# Main_Schematic.net
KiCad netlist of a schematic drawn in Altium Designer
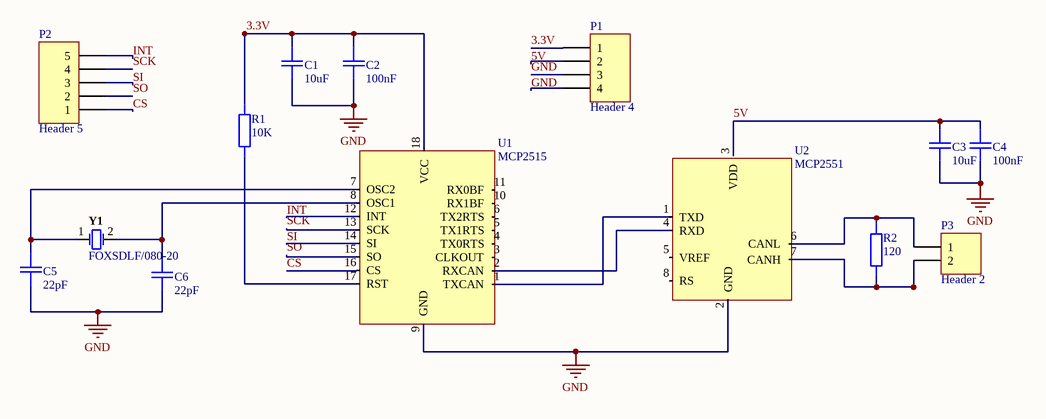
[diagram p0: Main Schematic.SchDoc]

(export (version "E")
  (design (tool "Eeschema 10.0.6"))
  (components
    (comp (ref "C1")
      (value "10uF")
      (footprint "CAP0805")
      (fields
        (field (name "VOLTAGE") "10V")
        (field (name "TOLERANCE") "20%")
        (field (name "Comment") "Capacitor")
      )
      (libsource (lib "Orbit") (part "Capacitor"))
    )
    (comp (ref "C2")
      (value "100nF")
      (footprint "CAP0805")
      (fields
        (field (name "VOLTAGE") "16V")
        (field (name "TOLERANCE") "10%")
        (field (name "Comment") "Capacitor")
      )
      (libsource (lib "Orbit") (part "Capacitor"))
    )
    (comp (ref "C3")
      (value "10uF")
      (footprint "CAP0805")
      (fields
        (field (name "VOLTAGE") "10V")
        (field (name "TOLERANCE") "20%")
        (field (name "Comment") "Capacitor")
      )
      (libsource (lib "Orbit") (part "Capacitor"))
    )
    (comp (ref "C4")
      (value "100nF")
      (footprint "CAP0805")
      (fields
        (field (name "VOLTAGE") "16V")
        (field (name "TOLERANCE") "10%")
        (field (name "Comment") "Capacitor")
      )
      (libsource (lib "Orbit") (part "Capacitor"))
    )
    (comp (ref "C5")
      (value "22pF")
      (footprint "CAP0805")
      (fields
        (field (name "VOLTAGE") "16V")
        (field (name "TOLERANCE") "10%")
        (field (name "Comment") "Capacitor")
      )
      (libsource (lib "Orbit") (part "Capacitor"))
    )
    (comp (ref "C6")
      (value "22pF")
      (footprint "CAP0805")
      (fields
        (field (name "VOLTAGE") "16V")
        (field (name "TOLERANCE") "10%")
        (field (name "Comment") "Capacitor")
      )
      (libsource (lib "Orbit") (part "Capacitor"))
    )
    (comp (ref "P1")
      (value "Header 4")
      (footprint "HDR1X4")
      (description "Header, 4-Pin")
      (fields (field (name "PUBLISHER") "Altium Limited"))
      (libsource (lib "Miscellaneous Connectors") (part "Header 4"))
    )
    (comp (ref "P2")
      (value "Header 5")
      (footprint "HDR1X5")
      (description "Header, 5-Pin")
      (fields (field (name "PUBLISHER") "Altium Limited"))
      (libsource (lib "Miscellaneous Connectors") (part "Header 5"))
    )
    (comp (ref "P3")
      (value "Header 2")
      (footprint "HDR1X2")
      (description "Header, 2-Pin")
      (fields (field (name "PUBLISHER") "Altium Limited"))
      (libsource (lib "Miscellaneous Connectors") (part "Header 2"))
    )
    (comp (ref "R1")
      (value "10K")
      (footprint "6-0805_L")
      (fields (field (name "TOLERANCE") "1%") (field (name "Comment") "Resistor"))
      (libsource (lib "Orbit") (part "Resistor"))
    )
    (comp (ref "R2")
      (value "120")
      (footprint "6-0805_L")
      (fields (field (name "TOLERANCE") "1%") (field (name "Comment") "Resistor"))
      (libsource (lib "Orbit") (part "Resistor"))
    )
    (comp (ref "U1")
      (value "MCP2515")
      (footprint "TSSOP 20-lead 4.4mm")
      (libsource (lib "Orbit") (part "MCP2515"))
    )
    (comp (ref "U2")
      (value "MCP2551")
      (footprint "SOIC 8-LEAD SN")
      (libsource (lib "Orbit") (part "MCP2551"))
    )
    (comp (ref "Y1")
      (value "FOXSDLF/080-20")
      (footprint "FOX-HC49SDLF_V")
      (description "Resistance Weld Crystal, 8 MHz, +/- 30 ppm, -20 to 70 degC, 2-Pin SMD, RoHS, Tape and Reel")
      (fields (field (name "MANUFACTURER") "FOX Electronics") (field (name "TOLERANCE") "50ppm"))
      (libsource (lib "Altium Content Vault") (part "XTAL-1-2-2"))
    )
  )
  (nets
    (net (code "1") (name "/3.3V") (class "Default")
      (node (ref "C1") (pin "1") (pinfunction "1_1") (pintype "passive"))
      (node (ref "C2") (pin "1") (pinfunction "1_1") (pintype "passive"))
      (node (ref "P1") (pin "1") (pinfunction "1_1") (pintype "passive"))
      (node (ref "R1") (pin "2") (pinfunction "2_2") (pintype "passive"))
      (node (ref "U1") (pin "18") (pinfunction "VCC_18") (pintype "power_in"))
    )
    (net (code "2") (name "/5V") (class "Default")
      (node (ref "C3") (pin "1") (pinfunction "1_1") (pintype "passive"))
      (node (ref "C4") (pin "1") (pinfunction "1_1") (pintype "passive"))
      (node (ref "P1") (pin "2") (pinfunction "2_2") (pintype "passive"))
      (node (ref "U2") (pin "3") (pinfunction "VDD_3") (pintype "power_in"))
    )
    (net (code "3") (name "/CS") (class "Default")
      (node (ref "P2") (pin "1") (pinfunction "1_1") (pintype "passive"))
      (node (ref "U1") (pin "16") (pinfunction "CS_16") (pintype "passive"))
    )
    (net (code "4") (name "/INT") (class "Default")
      (node (ref "P2") (pin "5") (pinfunction "5_5") (pintype "passive"))
      (node (ref "U1") (pin "12") (pinfunction "INT_12") (pintype "passive"))
    )
    (net (code "5") (name "/SCK") (class "Default")
      (node (ref "P2") (pin "4") (pinfunction "4_4") (pintype "passive"))
      (node (ref "U1") (pin "13") (pinfunction "SCK_13") (pintype "input"))
    )
    (net (code "6") (name "/SI") (class "Default")
      (node (ref "P2") (pin "3") (pinfunction "3_3") (pintype "passive"))
      (node (ref "U1") (pin "14") (pinfunction "SI_14") (pintype "input"))
    )
    (net (code "7") (name "/SO") (class "Default")
      (node (ref "P2") (pin "2") (pinfunction "2_2") (pintype "passive"))
      (node (ref "U1") (pin "15") (pinfunction "SO_15") (pintype "output"))
    )
    (net (code "8") (name "GND") (class "Default")
      (node (ref "C1") (pin "2") (pinfunction "2_2") (pintype "passive"))
      (node (ref "C2") (pin "2") (pinfunction "2_2") (pintype "passive"))
      (node (ref "C3") (pin "2") (pinfunction "2_2") (pintype "passive"))
      (node (ref "C4") (pin "2") (pinfunction "2_2") (pintype "passive"))
      (node (ref "C5") (pin "2") (pinfunction "2_2") (pintype "passive"))
      (node (ref "C6") (pin "2") (pinfunction "2_2") (pintype "passive"))
      (node (ref "P1") (pin "3") (pinfunction "3_3") (pintype "passive"))
      (node (ref "P1") (pin "4") (pinfunction "4_4") (pintype "passive"))
      (node (ref "U1") (pin "9") (pinfunction "GND_9") (pintype "power_in"))
      (node (ref "U2") (pin "2") (pinfunction "GND_2") (pintype "power_in"))
    )
    (net (code "9") (name "Net-(U1-OSC1)") (class "Default")
      (node (ref "C6") (pin "1") (pinfunction "1_1") (pintype "passive"))
      (node (ref "U1") (pin "8") (pinfunction "OSC1_8") (pintype "passive"))
      (node (ref "Y1") (pin "2") (pinfunction "2_2") (pintype "passive"))
    )
    (net (code "10") (name "Net-(U1-OSC2)") (class "Default")
      (node (ref "C5") (pin "1") (pinfunction "1_1") (pintype "passive"))
      (node (ref "U1") (pin "7") (pinfunction "OSC2_7") (pintype "passive"))
      (node (ref "Y1") (pin "1") (pinfunction "1_1") (pintype "passive"))
    )
    (net (code "11") (name "Net-(U1-RST)") (class "Default")
      (node (ref "R1") (pin "1") (pinfunction "1_1") (pintype "passive"))
      (node (ref "U1") (pin "17") (pinfunction "RST_17") (pintype "passive"))
    )
    (net (code "12") (name "Net-(U1-RXCAN)") (class "Default")
      (node (ref "U1") (pin "2") (pinfunction "RXCAN_2") (pintype "passive"))
      (node (ref "U2") (pin "4") (pinfunction "RXD_4") (pintype "input"))
    )
    (net (code "13") (name "Net-(U1-TXCAN)") (class "Default")
      (node (ref "U1") (pin "1") (pinfunction "TXCAN_1") (pintype "passive"))
      (node (ref "U2") (pin "1") (pinfunction "TXD_1") (pintype "output"))
    )
    (net (code "14") (name "Net-(U2-CANH)") (class "Default")
      (node (ref "P3") (pin "2") (pinfunction "2_2") (pintype "passive"))
      (node (ref "R2") (pin "1") (pinfunction "1_1") (pintype "passive"))
      (node (ref "U2") (pin "7") (pinfunction "CANH_7") (pintype "bidirectional"))
    )
    (net (code "15") (name "Net-(U2-CANL)") (class "Default")
      (node (ref "P3") (pin "1") (pinfunction "1_1") (pintype "passive"))
      (node (ref "R2") (pin "2") (pinfunction "2_2") (pintype "passive"))
      (node (ref "U2") (pin "6") (pinfunction "CANL_6") (pintype "bidirectional"))
    )
    (net (code "16") (name "unconnected-(U1-CLKOUT-Pad3)") (class "Default")
      (node (ref "U1") (pin "3") (pinfunction "CLKOUT_3") (pintype "passive"))
    )
    (net (code "17") (name "unconnected-(U1-RX0BF-Pad11)") (class "Default")
      (node (ref "U1") (pin "11") (pinfunction "RX0BF_11") (pintype "passive"))
    )
    (net (code "18") (name "unconnected-(U1-RX1BF-Pad10)") (class "Default")
      (node (ref "U1") (pin "10") (pinfunction "RX1BF_10") (pintype "passive"))
    )
    (net (code "19") (name "unconnected-(U1-TX0RTS-Pad4)") (class "Default")
      (node (ref "U1") (pin "4") (pinfunction "TX0RTS_4") (pintype "passive"))
    )
    (net (code "20") (name "unconnected-(U1-TX1RTS-Pad5)") (class "Default")
      (node (ref "U1") (pin "5") (pinfunction "TX1RTS_5") (pintype "passive"))
    )
    (net (code "21") (name "unconnected-(U1-TX2RTS-Pad6)") (class "Default")
      (node (ref "U1") (pin "6") (pinfunction "TX2RTS_6") (pintype "passive"))
    )
    (net (code "22") (name "unconnected-(U2-RS-Pad8)") (class "Default")
      (node (ref "U2") (pin "8") (pinfunction "RS_8") (pintype "input"))
    )
    (net (code "23") (name "unconnected-(U2-VREF-Pad5)") (class "Default")
      (node (ref "U2") (pin "5") (pinfunction "VREF_5") (pintype "input"))
    )
  )
)
